# CDCDCDC_12V.net
KiCad netlist of a schematic drawn in Altium Designer
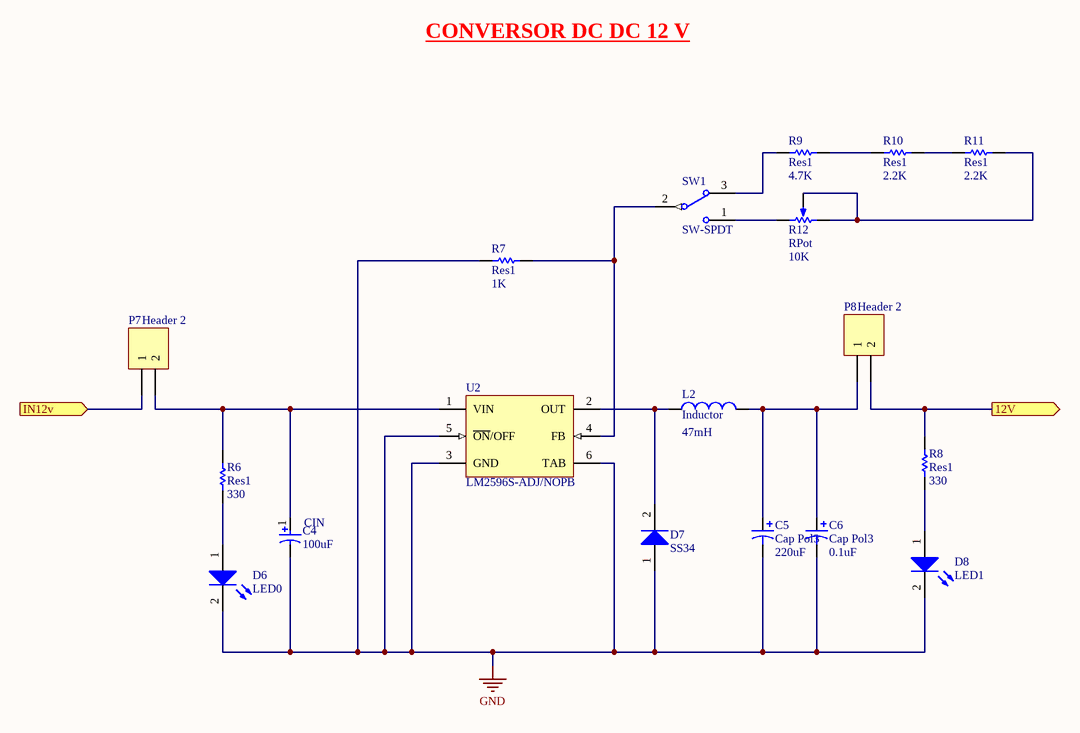
[diagram p0: CDCDCDC_12V.SchDoc]

(export (version "E")
  (design (tool "Eeschema 10.0.6"))
  (components
    (comp (ref "C4")
      (value "100uF")
      (footprint "NIC-UWT1H101MNL1GS_N")
      (fields (field (name "MANUFACTURER") "Nichicon"))
      (libsource (lib "Schlib1") (part "CMP-2000-07373-1"))
    )
    (comp (ref "C5")
      (value "Cap Pol3")
      (footprint "1812")
      (description "Polarized Capacitor (Surface Mount)")
      (fields (field (name "ALTIUM_VALUE") "220uF") (field (name "PUBLISHER") "Altium Limited"))
      (libsource (lib "Miscellaneous Devices") (part "Cap Pol3"))
    )
    (comp (ref "C6")
      (value "Cap Pol3")
      (footprint "1812")
      (description "Polarized Capacitor (Surface Mount)")
      (fields (field (name "ALTIUM_VALUE") "0.1uF") (field (name "PUBLISHER") "Altium Limited"))
      (libsource (lib "Miscellaneous Devices") (part "Cap Pol3"))
    )
    (comp (ref "D6")
      (value "LED0")
      (footprint "LED-0")
      (description "Typical INFRARED GaAs LED")
      (fields (field (name "PUBLISHER") "Altium Limited"))
      (libsource (lib "Miscellaneous Devices") (part "LED0"))
    )
    (comp (ref "D7")
      (value "SS34")
      (footprint "SMC")
      (description "Default Diode")
      (fields (field (name "PUBLISHER") "Altium Limited"))
      (libsource (lib "Miscellaneous Devices") (part "Diode"))
    )
    (comp (ref "D8")
      (value "LED1")
      (footprint "LED-0")
      (description "Typical INFRARED GaAs LED")
      (fields (field (name "PUBLISHER") "Altium Limited"))
      (libsource (lib "Miscellaneous Devices") (part "LED0"))
    )
    (comp (ref "L2")
      (value "Inductor")
      (footprint "0402-A")
      (fields (field (name "ALTIUM_VALUE") "47mH") (field (name "PUBLISHER") "Altium Limited"))
      (libsource (lib "Miscellaneous Devices") (part "Inductor"))
    )
    (comp (ref "P7")
      (value "Header 2")
      (footprint "HDR1X2")
      (description "Header, 2-Pin")
      (fields (field (name "PUBLISHER") "Altium Limited"))
      (libsource (lib "Miscellaneous Connectors") (part "Header 2"))
    )
    (comp (ref "P8")
      (value "Header 2")
      (footprint "HDR1X2")
      (description "Header, 2-Pin")
      (fields (field (name "PUBLISHER") "Altium Limited"))
      (libsource (lib "Miscellaneous Connectors") (part "Header 2"))
    )
    (comp (ref "R6")
      (value "Res1")
      (footprint "AXIAL-0.3")
      (description "Resistor")
      (fields (field (name "ALTIUM_VALUE") "330") (field (name "PUBLISHER") "Altium Limited"))
      (libsource (lib "Miscellaneous Devices") (part "Res1"))
    )
    (comp (ref "R7")
      (value "Res1")
      (footprint "AXIAL-0.3")
      (description "Resistor")
      (fields (field (name "ALTIUM_VALUE") "1K") (field (name "PUBLISHER") "Altium Limited"))
      (libsource (lib "Miscellaneous Devices") (part "Res1"))
    )
    (comp (ref "R8")
      (value "Res1")
      (footprint "AXIAL-0.3")
      (description "Resistor")
      (fields (field (name "ALTIUM_VALUE") "330") (field (name "PUBLISHER") "Altium Limited"))
      (libsource (lib "Miscellaneous Devices") (part "Res1"))
    )
    (comp (ref "R9")
      (value "Res1")
      (footprint "AXIAL-0.3")
      (description "Resistor")
      (fields (field (name "ALTIUM_VALUE") "4.7K") (field (name "PUBLISHER") "Altium Limited"))
      (libsource (lib "Miscellaneous Devices") (part "Res1"))
    )
    (comp (ref "R10")
      (value "Res1")
      (footprint "AXIAL-0.3")
      (description "Resistor")
      (fields (field (name "ALTIUM_VALUE") "2.2K") (field (name "PUBLISHER") "Altium Limited"))
      (libsource (lib "Miscellaneous Devices") (part "Res1"))
    )
    (comp (ref "R11")
      (value "Res1")
      (footprint "AXIAL-0.3")
      (description "Resistor")
      (fields (field (name "ALTIUM_VALUE") "2.2K") (field (name "PUBLISHER") "Altium Limited"))
      (libsource (lib "Miscellaneous Devices") (part "Res1"))
    )
    (comp (ref "R12")
      (value "RPot")
      (footprint "VR5")
      (description "Potentiometer")
      (fields (field (name "ALTIUM_VALUE") "10K") (field (name "PUBLISHER") "Altium Limited"))
      (libsource (lib "Miscellaneous Devices") (part "RPot"))
    )
    (comp (ref "SW1")
      (value "SW-SPDT")
      (footprint "TL36WW15050")
      (description "SPDT Subminiature Toggle Switch, Right Angle Mounting, Vertical Actuation")
      (fields (field (name "PUBLISHER") "Altium Limited"))
      (libsource (lib "Miscellaneous Devices") (part "SW-SPDT"))
    )
    (comp (ref "U2")
      (value "LM2596S-ADJ/NOPB")
      (footprint "KTT0005B_N")
      (description "SIMPLE SWITCHER® Power Converter 150 KHz 3A Step-Down Voltage Regulator, 5-pin TO-263, Pb-Free")
      (fields (field (name "MANUFACTURER") "Texas Instruments"))
      (libsource (lib "Schlib1") (part "CMP-0069-00271-3"))
    )
  )
  (nets
    (net (code "1") (name "/12V") (class "Default")
      (node (ref "P8") (pin "2") (pinfunction "2_2") (pintype "passive"))
      (node (ref "R8") (pin "2") (pinfunction "2_2") (pintype "passive"))
    )
    (net (code "2") (name "/IN12v") (class "Default")
      (node (ref "P7") (pin "1") (pinfunction "1_1") (pintype "passive"))
    )
    (net (code "3") (name "GND") (class "Default")
      (node (ref "C4") (pin "2") (pinfunction "2_2") (pintype "passive"))
      (node (ref "C5") (pin "2") (pinfunction "2_2") (pintype "passive"))
      (node (ref "C6") (pin "2") (pinfunction "2_2") (pintype "passive"))
      (node (ref "D6") (pin "2") (pinfunction "K_2") (pintype "passive"))
      (node (ref "D7") (pin "1") (pinfunction "A_1") (pintype "passive"))
      (node (ref "D8") (pin "2") (pinfunction "K_2") (pintype "passive"))
      (node (ref "R7") (pin "2") (pinfunction "2_2") (pintype "passive"))
      (node (ref "U2") (pin "3") (pinfunction "GND_3") (pintype "power_in"))
      (node (ref "U2") (pin "5") (pinfunction "~{ON}/OFF_5") (pintype "input"))
      (node (ref "U2") (pin "6") (pinfunction "TAB_6") (pintype "power_in"))
    )
    (net (code "4") (name "Net-(C5-Pad1)") (class "Default")
      (node (ref "C5") (pin "1") (pinfunction "1_1") (pintype "passive"))
      (node (ref "C6") (pin "1") (pinfunction "1_1") (pintype "passive"))
      (node (ref "L2") (pin "2") (pinfunction "2_2") (pintype "passive"))
      (node (ref "P8") (pin "1") (pinfunction "1_1") (pintype "passive"))
    )
    (net (code "5") (name "Net-(D6-A)") (class "Default")
      (node (ref "D6") (pin "1") (pinfunction "A_1") (pintype "passive"))
      (node (ref "R6") (pin "1") (pinfunction "1_1") (pintype "passive"))
    )
    (net (code "6") (name "Net-(D7-K)") (class "Default")
      (node (ref "D7") (pin "2") (pinfunction "K_2") (pintype "passive"))
      (node (ref "L2") (pin "1") (pinfunction "1_1") (pintype "passive"))
      (node (ref "U2") (pin "2") (pinfunction "OUT_2") (pintype "power_in"))
    )
    (net (code "7") (name "Net-(D8-A)") (class "Default")
      (node (ref "D8") (pin "1") (pinfunction "A_1") (pintype "passive"))
      (node (ref "R8") (pin "1") (pinfunction "1_1") (pintype "passive"))
    )
    (net (code "8") (name "Net-(R9-Pad2)") (class "Default")
      (node (ref "R9") (pin "2") (pinfunction "2_2") (pintype "passive"))
      (node (ref "SW1") (pin "3") (pinfunction "3_3") (pintype "passive"))
    )
    (net (code "9") (name "Net-(R10-Pad1)") (class "Default")
      (node (ref "R10") (pin "1") (pinfunction "1_1") (pintype "passive"))
      (node (ref "R11") (pin "2") (pinfunction "2_2") (pintype "passive"))
    )
    (net (code "10") (name "Net-(R10-Pad2)") (class "Default")
      (node (ref "R10") (pin "2") (pinfunction "2_2") (pintype "passive"))
      (node (ref "R9") (pin "1") (pinfunction "1_1") (pintype "passive"))
    )
    (net (code "11") (name "Net-(R12-BOT)") (class "Default")
      (node (ref "R12") (pin "2") (pinfunction "BOT_2") (pintype "passive"))
      (node (ref "SW1") (pin "1") (pinfunction "1_1") (pintype "passive"))
    )
    (net (code "12") (name "Net-(R12-TAP)") (class "Default")
      (node (ref "R11") (pin "1") (pinfunction "1_1") (pintype "passive"))
      (node (ref "R12") (pin "1") (pinfunction "TOP_1") (pintype "passive"))
      (node (ref "R12") (pin "3") (pinfunction "TAP_3") (pintype "passive"))
    )
    (net (code "13") (name "Net-(U2-FB)") (class "Default")
      (node (ref "R7") (pin "1") (pinfunction "1_1") (pintype "passive"))
      (node (ref "SW1") (pin "2") (pinfunction "2_2") (pintype "output"))
      (node (ref "U2") (pin "4") (pinfunction "FB_4") (pintype "input"))
    )
    (net (code "14") (name "Net-(U2-VIN)") (class "Default")
      (node (ref "C4") (pin "1") (pinfunction "1_1") (pintype "passive"))
      (node (ref "P7") (pin "2") (pinfunction "2_2") (pintype "passive"))
      (node (ref "R6") (pin "2") (pinfunction "2_2") (pintype "passive"))
      (node (ref "U2") (pin "1") (pinfunction "VIN_1") (pintype "power_in"))
    )
  )
)
